# main_chip.net
KiCad netlist of a schematic drawn in Altium Designer
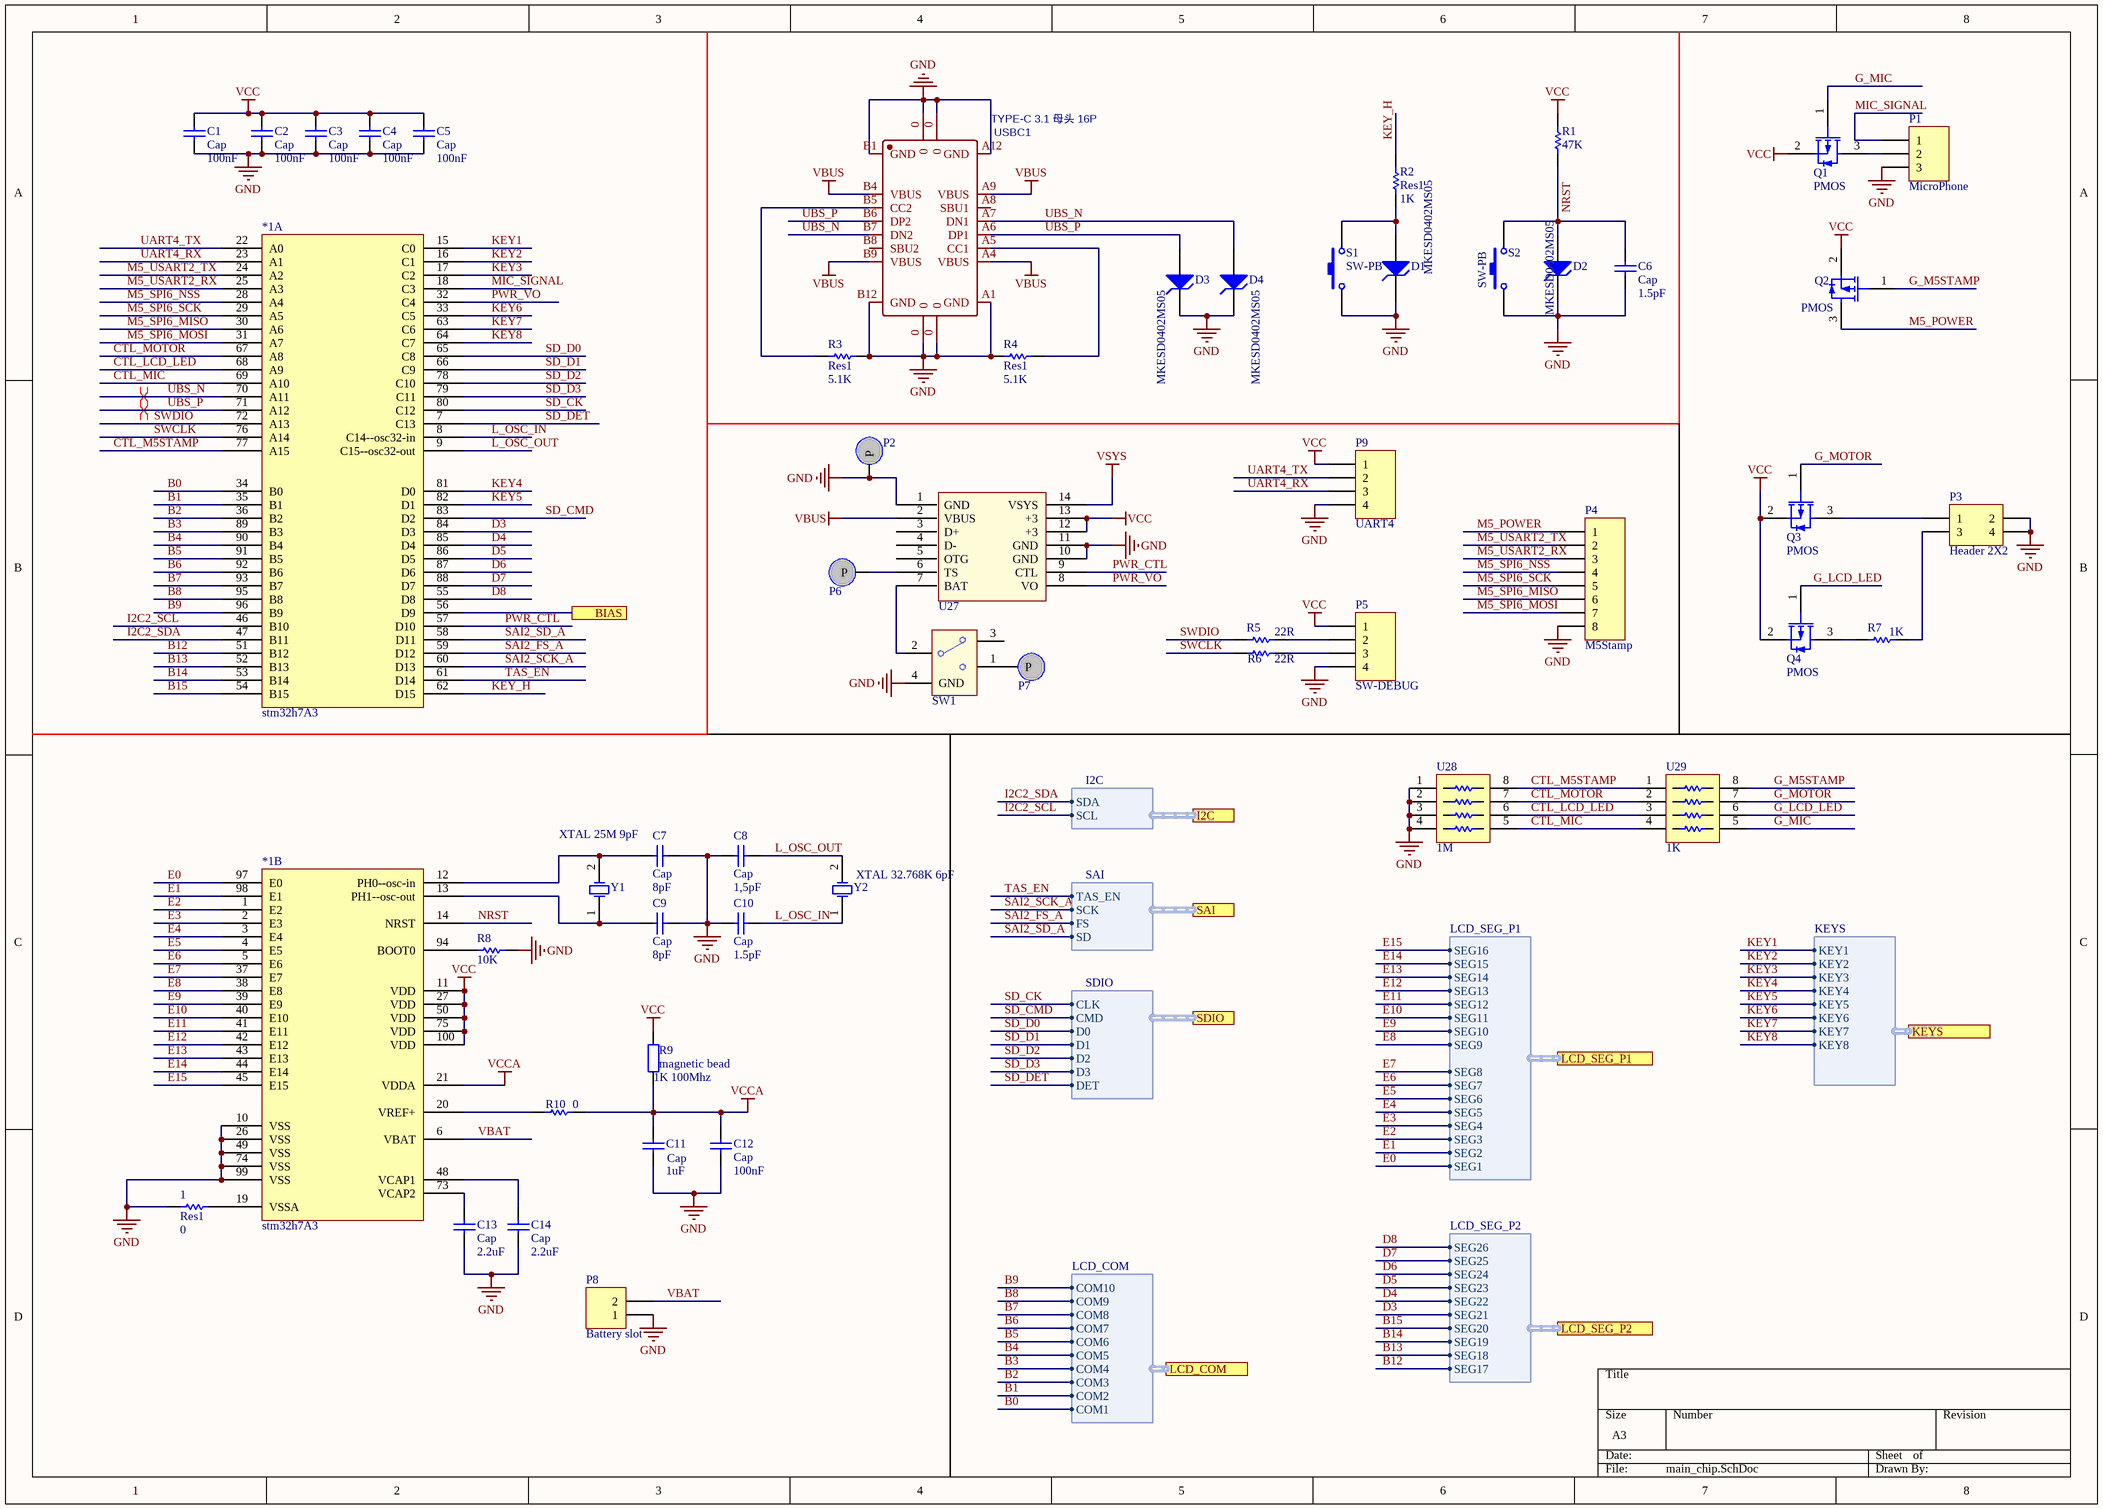
[diagram p0: main_chip.SchDoc]

(export (version "E")
  (design (tool "Eeschema 10.0.6"))
  (components
    (comp (ref "*1")
      (value "stm32h7A3")
      (footprint "CQFP-100")
      (libsource (lib "stm32h743") (part "stm32h743"))
    )
    (comp (ref "1")
      (value "Res1")
      (footprint "0402")
      (description "Resistor")
      (fields (field (name "ALTIUM_VALUE") "0") (field (name "PUBLISHER") "Altium Limited"))
      (libsource (lib "Miscellaneous Devices") (part "Res1"))
    )
    (comp (ref "C1")
      (value "Cap")
      (footprint "0402")
      (description "Capacitor")
      (fields (field (name "ALTIUM_VALUE") "100nF") (field (name "PUBLISHER") "Altium Limited"))
      (libsource (lib "Miscellaneous Devices") (part "Cap"))
    )
    (comp (ref "C2")
      (value "Cap")
      (footprint "0402")
      (description "Capacitor")
      (fields (field (name "ALTIUM_VALUE") "100nF") (field (name "PUBLISHER") "Altium Limited"))
      (libsource (lib "Miscellaneous Devices") (part "Cap"))
    )
    (comp (ref "C3")
      (value "Cap")
      (footprint "0402")
      (description "Capacitor")
      (fields (field (name "ALTIUM_VALUE") "100nF") (field (name "PUBLISHER") "Altium Limited"))
      (libsource (lib "Miscellaneous Devices") (part "Cap"))
    )
    (comp (ref "C4")
      (value "Cap")
      (footprint "0402")
      (description "Capacitor")
      (fields (field (name "ALTIUM_VALUE") "100nF") (field (name "PUBLISHER") "Altium Limited"))
      (libsource (lib "Miscellaneous Devices") (part "Cap"))
    )
    (comp (ref "C5")
      (value "Cap")
      (footprint "0402")
      (description "Capacitor")
      (fields (field (name "ALTIUM_VALUE") "100nF") (field (name "PUBLISHER") "Altium Limited"))
      (libsource (lib "Miscellaneous Devices") (part "Cap"))
    )
    (comp (ref "C6")
      (value "Cap")
      (footprint "0402")
      (description "Capacitor")
      (fields (field (name "ALTIUM_VALUE") "1.5pF") (field (name "PUBLISHER") "Altium Limited"))
      (libsource (lib "Miscellaneous Devices") (part "Cap"))
    )
    (comp (ref "C7")
      (value "Cap")
      (footprint "0402")
      (description "Capacitor")
      (fields (field (name "ALTIUM_VALUE") "8pF") (field (name "PUBLISHER") "Altium Limited"))
      (libsource (lib "Miscellaneous Devices") (part "Cap"))
    )
    (comp (ref "C8")
      (value "Cap")
      (footprint "0402")
      (description "Capacitor")
      (fields (field (name "ALTIUM_VALUE") "1,5pF") (field (name "PUBLISHER") "Altium Limited"))
      (libsource (lib "Miscellaneous Devices") (part "Cap"))
    )
    (comp (ref "C9")
      (value "Cap")
      (footprint "0402")
      (description "Capacitor")
      (fields (field (name "ALTIUM_VALUE") "8pF") (field (name "PUBLISHER") "Altium Limited"))
      (libsource (lib "Miscellaneous Devices") (part "Cap"))
    )
    (comp (ref "C10")
      (value "Cap")
      (footprint "0402")
      (description "Capacitor")
      (fields (field (name "ALTIUM_VALUE") "1.5pF") (field (name "PUBLISHER") "Altium Limited"))
      (libsource (lib "Miscellaneous Devices") (part "Cap"))
    )
    (comp (ref "C11")
      (value "Cap")
      (footprint "6-0805_L")
      (description "Capacitor")
      (fields (field (name "ALTIUM_VALUE") "1uF") (field (name "PUBLISHER") "Altium Limited"))
      (libsource (lib "Miscellaneous Devices") (part "Cap"))
    )
    (comp (ref "C12")
      (value "Cap")
      (footprint "0402")
      (description "Capacitor")
      (fields (field (name "ALTIUM_VALUE") "100nF") (field (name "PUBLISHER") "Altium Limited"))
      (libsource (lib "Miscellaneous Devices") (part "Cap"))
    )
    (comp (ref "C13")
      (value "Cap")
      (footprint "6-0805_L")
      (description "Capacitor")
      (fields (field (name "ALTIUM_VALUE") "2.2uF") (field (name "PUBLISHER") "Altium Limited"))
      (libsource (lib "Miscellaneous Devices") (part "Cap"))
    )
    (comp (ref "C14")
      (value "Cap")
      (footprint "6-0805_L")
      (description "Capacitor")
      (fields (field (name "ALTIUM_VALUE") "2.2uF") (field (name "PUBLISHER") "Altium Limited"))
      (libsource (lib "Miscellaneous Devices") (part "Cap"))
    )
    (comp (ref "D1")
      (value "MKESD0402MS05")
      (footprint "0402")
      (description "Zener Diode")
      (fields (field (name "PUBLISHER") "Altium Limited"))
      (libsource (lib "Miscellaneous Devices") (part "D Zener"))
    )
    (comp (ref "D2")
      (value "MKESD0402MS05")
      (footprint "0402")
      (description "Zener Diode")
      (fields (field (name "PUBLISHER") "Altium Limited"))
      (libsource (lib "Miscellaneous Devices") (part "D Zener"))
    )
    (comp (ref "D3")
      (value "MKESD0402MS05")
      (footprint "0402")
      (description "Zener Diode")
      (fields (field (name "PUBLISHER") "Altium Limited"))
      (libsource (lib "Miscellaneous Devices") (part "D Zener"))
    )
    (comp (ref "D4")
      (value "MKESD0402MS05")
      (footprint "0402")
      (description "Zener Diode")
      (fields (field (name "PUBLISHER") "Altium Limited"))
      (libsource (lib "Miscellaneous Devices") (part "D Zener"))
    )
    (comp (ref "P1")
      (value "MicroPhone")
      (footprint "HDR1X3")
      (description "Header, 3-Pin")
      (fields (field (name "PUBLISHER") "Altium Limited"))
      (libsource (lib "Miscellaneous Connectors") (part "Header 3"))
    )
    (comp (ref "P2") (value "Point") (footprint "Point") (libsource (lib "cl_sch") (part "Point")))
    (comp (ref "P3")
      (value "Header 2X2")
      (footprint "HDR2X2")
      (description "Header, 2-Pin, Dual row")
      (fields (field (name "PUBLISHER") "Altium Limited"))
      (libsource (lib "Miscellaneous Connectors") (part "Header 2X2"))
    )
    (comp (ref "P4")
      (value "M5Stamp")
      (footprint "HDR1X8")
      (description "Header, 8-Pin")
      (fields (field (name "PUBLISHER") "Altium Limited"))
      (libsource (lib "Miscellaneous Connectors") (part "Header 8"))
    )
    (comp (ref "P5")
      (value "SW-DEBUG")
      (footprint "HDR1X4")
      (description "Header, 4-Pin")
      (fields (field (name "PUBLISHER") "Altium Limited"))
      (libsource (lib "Miscellaneous Connectors") (part "Header 4"))
    )
    (comp (ref "P6") (value "Point") (footprint "Point") (libsource (lib "cl_sch") (part "Point")))
    (comp (ref "P7") (value "Point") (footprint "Point") (libsource (lib "cl_sch") (part "Point")))
    (comp (ref "P8")
      (value "Battery slot")
      (footprint "CR1220-SLOT")
      (description "Header, 2-Pin")
      (fields (field (name "PUBLISHER") "Altium Limited"))
      (libsource (lib "Miscellaneous Connectors") (part "Header 2"))
    )
    (comp (ref "P9")
      (value "UART4")
      (footprint "HDR1X4")
      (description "Header, 4-Pin")
      (fields (field (name "PUBLISHER") "Altium Limited"))
      (libsource (lib "Miscellaneous Connectors") (part "Header 4"))
    )
    (comp (ref "Q1") (value "PMOS") (footprint "SOT23-3") (libsource (lib "cl_sch") (part "PMOS")))
    (comp (ref "Q2") (value "PMOS") (footprint "SOT23-3") (libsource (lib "cl_sch") (part "PMOS")))
    (comp (ref "Q3") (value "PMOS") (footprint "SOT23-3") (libsource (lib "cl_sch") (part "PMOS")))
    (comp (ref "Q4") (value "PMOS") (footprint "SOT23-3") (libsource (lib "cl_sch") (part "PMOS")))
    (comp (ref "R1")
      (value "47K")
      (footprint "0402")
      (description "Resistor")
      (fields (field (name "Comment") "Res1") (field (name "PUBLISHER") "Altium Limited"))
      (libsource (lib "Miscellaneous Devices") (part "Res1"))
    )
    (comp (ref "R2")
      (value "Res1")
      (footprint "0402")
      (description "Resistor")
      (fields (field (name "ALTIUM_VALUE") "1K") (field (name "PUBLISHER") "Altium Limited"))
      (libsource (lib "Miscellaneous Devices") (part "Res1"))
    )
    (comp (ref "R3")
      (value "Res1")
      (footprint "0402")
      (description "Resistor")
      (fields (field (name "ALTIUM_VALUE") "5.1K") (field (name "PUBLISHER") "Altium Limited"))
      (libsource (lib "Miscellaneous Devices") (part "Res1"))
    )
    (comp (ref "R4")
      (value "Res1")
      (footprint "0402")
      (description "Resistor")
      (fields (field (name "ALTIUM_VALUE") "5.1K") (field (name "PUBLISHER") "Altium Limited"))
      (libsource (lib "Miscellaneous Devices") (part "Res1"))
    )
    (comp (ref "R5")
      (value "22R")
      (footprint "0402")
      (description "Resistor")
      (fields (field (name "Comment") "Res1") (field (name "PUBLISHER") "Altium Limited"))
      (libsource (lib "Miscellaneous Devices") (part "Res1"))
    )
    (comp (ref "R6")
      (value "22R")
      (footprint "0402")
      (description "Resistor")
      (fields (field (name "Comment") "Res1") (field (name "PUBLISHER") "Altium Limited"))
      (libsource (lib "Miscellaneous Devices") (part "Res1"))
    )
    (comp (ref "R7")
      (value "1K")
      (footprint "0402")
      (description "Resistor")
      (fields (field (name "Comment") "Res1") (field (name "PUBLISHER") "Altium Limited"))
      (libsource (lib "Miscellaneous Devices") (part "Res1"))
    )
    (comp (ref "R8")
      (value "10K")
      (footprint "0402")
      (description "Resistor")
      (fields (field (name "Comment") "Res1") (field (name "PUBLISHER") "Altium Limited"))
      (libsource (lib "Miscellaneous Devices") (part "Res1"))
    )
    (comp (ref "R9")
      (value "magnetic bead")
      (footprint "0402")
      (description "Resistor")
      (fields (field (name "ALTIUM_VALUE") "1K 100Mhz") (field (name "PUBLISHER") "Altium Limited"))
      (libsource (lib "Miscellaneous Devices") (part "Res2"))
    )
    (comp (ref "R10")
      (value "0")
      (footprint "0402")
      (description "Resistor")
      (fields (field (name "Comment") "Res1") (field (name "PUBLISHER") "Altium Limited"))
      (libsource (lib "Miscellaneous Devices") (part "Res1"))
    )
    (comp (ref "S1")
      (value "SW-PB")
      (footprint "BTN_0304")
      (description "Switch")
      (fields (field (name "PUBLISHER") "Altium Limited"))
      (libsource (lib "Miscellaneous Devices") (part "SW-PB"))
    )
    (comp (ref "S2")
      (value "SW-PB")
      (footprint "BTN_0304")
      (description "Switch")
      (fields (field (name "PUBLISHER") "Altium Limited"))
      (libsource (lib "Miscellaneous Devices") (part "SW-PB"))
    )
    (comp (ref "SW1") (value "SK-12D07VG3") (footprint "switch") (libsource (lib "cl_sch") (part "SW-8.6mm")))
    (comp (ref "U27") (value "my_power") (footprint "my_power") (libsource (lib "cl_sch") (part "my_power")))
    (comp (ref "U28") (value "1M") (footprint "0603_RES_BATCH") (libsource (lib "cl_sch") (part "RES_BATCH")))
    (comp (ref "U29") (value "1K") (footprint "0603_RES_BATCH") (libsource (lib "cl_sch") (part "RES_BATCH")))
    (comp (ref "USBC1")
      (value "TYPE-C 3.1 母头 16P")
      (footprint "USB-C-SMD_16P")
      (libsource (lib "type-c-sch") (part "TYPE-C 3.1 母头 16P"))
    )
    (comp (ref "Y1")
      (value "XTAL 25M 9pF")
      (footprint "xtal_5032_25Mhz")
      (description "Crystal Oscillator")
      (fields (field (name "PUBLISHER") "Altium Limited"))
      (libsource (lib "Miscellaneous Devices") (part "XTAL"))
    )
    (comp (ref "Y2")
      (value "XTAL 32.768K 6pF")
      (footprint "xtal_3215_32768")
      (description "Crystal Oscillator")
      (fields (field (name "PUBLISHER") "Altium Limited"))
      (libsource (lib "Miscellaneous Devices") (part "XTAL"))
    )
  )
  (nets
    (net (code "8") (name "/B0") (class "Default")
      (node (ref "*1") (pin "34") (pinfunction "B0_34") (pintype "passive"))
    )
    (net (code "9") (name "/B1") (class "Default")
      (node (ref "*1") (pin "35") (pinfunction "B1_35") (pintype "passive"))
    )
    (net (code "10") (name "/B2") (class "Default")
      (node (ref "*1") (pin "36") (pinfunction "B2_36") (pintype "passive"))
    )
    (net (code "11") (name "/B3") (class "Default")
      (node (ref "*1") (pin "89") (pinfunction "B3_89") (pintype "passive"))
    )
    (net (code "12") (name "/B4") (class "Default")
      (node (ref "*1") (pin "90") (pinfunction "B4_90") (pintype "passive"))
    )
    (net (code "13") (name "/B5") (class "Default")
      (node (ref "*1") (pin "91") (pinfunction "B5_91") (pintype "passive"))
    )
    (net (code "14") (name "/B6") (class "Default")
      (node (ref "*1") (pin "92") (pinfunction "B6_92") (pintype "passive"))
    )
    (net (code "15") (name "/B7") (class "Default")
      (node (ref "*1") (pin "93") (pinfunction "B7_93") (pintype "passive"))
    )
    (net (code "16") (name "/B8") (class "Default")
      (node (ref "*1") (pin "95") (pinfunction "B8_95") (pintype "passive"))
    )
    (net (code "17") (name "/B9") (class "Default")
      (node (ref "*1") (pin "96") (pinfunction "B9_96") (pintype "passive"))
    )
    (net (code "18") (name "/B12") (class "Default")
      (node (ref "*1") (pin "51") (pinfunction "B12_51") (pintype "passive"))
    )
    (net (code "19") (name "/B13") (class "Default")
      (node (ref "*1") (pin "52") (pinfunction "B13_52") (pintype "passive"))
    )
    (net (code "20") (name "/B14") (class "Default")
      (node (ref "*1") (pin "53") (pinfunction "B14_53") (pintype "passive"))
    )
    (net (code "21") (name "/B15") (class "Default")
      (node (ref "*1") (pin "54") (pinfunction "B15_54") (pintype "passive"))
    )
    (net (code "22") (name "/BIAS") (class "Default")
      (node (ref "*1") (pin "56") (pinfunction "D9_56") (pintype "passive"))
    )
    (net (code "23") (name "/CTL_LCD_LED") (class "Default")
      (node (ref "*1") (pin "68") (pinfunction "A9_68") (pintype "passive"))
      (node (ref "U28") (pin "6") (pinfunction "6_6") (pintype "passive"))
      (node (ref "U29") (pin "3") (pinfunction "3_3") (pintype "passive"))
    )
    (net (code "24") (name "/CTL_M5STAMP") (class "Default")
      (node (ref "*1") (pin "77") (pinfunction "A15_77") (pintype "passive"))
      (node (ref "U28") (pin "8") (pinfunction "8_8") (pintype "passive"))
      (node (ref "U29") (pin "1") (pinfunction "1_1") (pintype "passive"))
    )
    (net (code "25") (name "/CTL_MIC") (class "Default")
      (node (ref "*1") (pin "69") (pinfunction "A10_69") (pintype "passive"))
      (node (ref "U28") (pin "5") (pinfunction "5_5") (pintype "passive"))
      (node (ref "U29") (pin "4") (pinfunction "4_4") (pintype "passive"))
    )
    (net (code "26") (name "/CTL_MOTOR") (class "Default")
      (node (ref "*1") (pin "67") (pinfunction "A8_67") (pintype "passive"))
      (node (ref "U28") (pin "7") (pinfunction "7_7") (pintype "passive"))
      (node (ref "U29") (pin "2") (pinfunction "2_2") (pintype "passive"))
    )
    (net (code "27") (name "/D3") (class "Default")
      (node (ref "*1") (pin "84") (pinfunction "D3_84") (pintype "passive"))
    )
    (net (code "28") (name "/D4") (class "Default")
      (node (ref "*1") (pin "85") (pinfunction "D4_85") (pintype "passive"))
    )
    (net (code "29") (name "/D5") (class "Default")
      (node (ref "*1") (pin "86") (pinfunction "D5_86") (pintype "passive"))
    )
    (net (code "30") (name "/D6") (class "Default")
      (node (ref "*1") (pin "87") (pinfunction "D6_87") (pintype "passive"))
    )
    (net (code "31") (name "/D7") (class "Default")
      (node (ref "*1") (pin "88") (pinfunction "D7_88") (pintype "passive"))
    )
    (net (code "32") (name "/D8") (class "Default")
      (node (ref "*1") (pin "55") (pinfunction "D8_55") (pintype "passive"))
    )
    (net (code "33") (name "/E0") (class "Default")
      (node (ref "*1") (pin "97") (pinfunction "E0_97") (pintype "passive"))
    )
    (net (code "34") (name "/E1") (class "Default")
      (node (ref "*1") (pin "98") (pinfunction "E1_98") (pintype "passive"))
    )
    (net (code "35") (name "/E2") (class "Default")
      (node (ref "*1") (pin "1") (pinfunction "E2_1") (pintype "passive"))
    )
    (net (code "36") (name "/E3") (class "Default")
      (node (ref "*1") (pin "2") (pinfunction "E3_2") (pintype "passive"))
    )
    (net (code "37") (name "/E4") (class "Default")
      (node (ref "*1") (pin "3") (pinfunction "E4_3") (pintype "passive"))
    )
    (net (code "38") (name "/E5") (class "Default")
      (node (ref "*1") (pin "4") (pinfunction "E5_4") (pintype "passive"))
    )
    (net (code "39") (name "/E6") (class "Default")
      (node (ref "*1") (pin "5") (pinfunction "E6_5") (pintype "passive"))
    )
    (net (code "40") (name "/E7") (class "Default")
      (node (ref "*1") (pin "37") (pinfunction "E7_37") (pintype "passive"))
    )
    (net (code "41") (name "/E8") (class "Default")
      (node (ref "*1") (pin "38") (pinfunction "E8_38") (pintype "passive"))
    )
    (net (code "42") (name "/E9") (class "Default")
      (node (ref "*1") (pin "39") (pinfunction "E9_39") (pintype "passive"))
    )
    (net (code "43") (name "/E10") (class "Default")
      (node (ref "*1") (pin "40") (pinfunction "E10_40") (pintype "passive"))
    )
    (net (code "44") (name "/E11") (class "Default")
      (node (ref "*1") (pin "41") (pinfunction "E11_41") (pintype "passive"))
    )
    (net (code "45") (name "/E12") (class "Default")
      (node (ref "*1") (pin "42") (pinfunction "E12_42") (pintype "passive"))
    )
    (net (code "46") (name "/E13") (class "Default")
      (node (ref "*1") (pin "43") (pinfunction "E13_43") (pintype "passive"))
    )
    (net (code "47") (name "/E14") (class "Default")
      (node (ref "*1") (pin "44") (pinfunction "E14_44") (pintype "passive"))
    )
    (net (code "48") (name "/E15") (class "Default")
      (node (ref "*1") (pin "45") (pinfunction "E15_45") (pintype "passive"))
    )
    (net (code "49") (name "/G_LCD_LED") (class "Default")
      (node (ref "Q4") (pin "1") (pinfunction "G_1") (pintype "passive"))
      (node (ref "U29") (pin "6") (pinfunction "6_6") (pintype "passive"))
    )
    (net (code "50") (name "/G_M5STAMP") (class "Default")
      (node (ref "Q2") (pin "1") (pinfunction "G_1") (pintype "passive"))
      (node (ref "U29") (pin "8") (pinfunction "8_8") (pintype "passive"))
    )
    (net (code "51") (name "/G_MIC") (class "Default")
      (node (ref "Q1") (pin "1") (pinfunction "G_1") (pintype "passive"))
      (node (ref "U29") (pin "5") (pinfunction "5_5") (pintype "passive"))
    )
    (net (code "52") (name "/G_MOTOR") (class "Default")
      (node (ref "Q3") (pin "1") (pinfunction "G_1") (pintype "passive"))
      (node (ref "U29") (pin "7") (pinfunction "7_7") (pintype "passive"))
    )
    (net (code "53") (name "/I2C2_SCL") (class "Default")
      (node (ref "*1") (pin "46") (pinfunction "B10_46") (pintype "passive"))
    )
    (net (code "54") (name "/I2C2_SDA") (class "Default")
      (node (ref "*1") (pin "47") (pinfunction "B11_47") (pintype "passive"))
    )
    (net (code "55") (name "/KEY1") (class "Default")
      (node (ref "*1") (pin "15") (pinfunction "C0_15") (pintype "passive"))
    )
    (net (code "56") (name "/KEY2") (class "Default")
      (node (ref "*1") (pin "16") (pinfunction "C1_16") (pintype "passive"))
    )
    (net (code "57") (name "/KEY3") (class "Default")
      (node (ref "*1") (pin "17") (pinfunction "C2_17") (pintype "passive"))
    )
    (net (code "58") (name "/KEY4") (class "Default")
      (node (ref "*1") (pin "81") (pinfunction "D0_81") (pintype "passive"))
    )
    (net (code "59") (name "/KEY5") (class "Default")
      (node (ref "*1") (pin "82") (pinfunction "D1_82") (pintype "passive"))
    )
    (net (code "60") (name "/KEY6") (class "Default")
      (node (ref "*1") (pin "33") (pinfunction "C5_33") (pintype "passive"))
    )
    (net (code "61") (name "/KEY7") (class "Default")
      (node (ref "*1") (pin "63") (pinfunction "C6_63") (pintype "passive"))
    )
    (net (code "62") (name "/KEY8") (class "Default")
      (node (ref "*1") (pin "64") (pinfunction "C7_64") (pintype "passive"))
    )
    (net (code "63") (name "/KEY_H") (class "Default")
      (node (ref "*1") (pin "62") (pinfunction "D15_62") (pintype "passive"))
      (node (ref "R2") (pin "1") (pinfunction "1_1") (pintype "passive"))
    )
    (net (code "64") (name "/L_OSC_IN") (class "Default")
      (node (ref "*1") (pin "8") (pinfunction "C14--osc32-in_8") (pintype "passive"))
      (node (ref "C10") (pin "1") (pinfunction "1_1") (pintype "passive"))
      (node (ref "Y2") (pin "1") (pinfunction "OSC1_1") (pintype "passive"))
    )
    (net (code "65") (name "/L_OSC_OUT") (class "Default")
      (node (ref "*1") (pin "9") (pinfunction "C15--osc32-out_9") (pintype "passive"))
      (node (ref "C8") (pin "1") (pinfunction "1_1") (pintype "passive"))
      (node (ref "Y2") (pin "2") (pinfunction "OSC2_2") (pintype "passive"))
    )
    (net (code "66") (name "/M5_POWER") (class "Default")
      (node (ref "P4") (pin "1") (pinfunction "1_1") (pintype "passive"))
      (node (ref "Q2") (pin "3") (pinfunction "D_3") (pintype "passive"))
    )
    (net (code "67") (name "/M5_SPI6_MISO") (class "Default")
      (node (ref "*1") (pin "30") (pinfunction "A6_30") (pintype "passive"))
      (node (ref "P4") (pin "6") (pinfunction "6_6") (pintype "passive"))
    )
    (net (code "68") (name "/M5_SPI6_MOSI") (class "Default")
      (node (ref "*1") (pin "31") (pinfunction "A7_31") (pintype "passive"))
      (node (ref "P4") (pin "7") (pinfunction "7_7") (pintype "passive"))
    )
    (net (code "69") (name "/M5_SPI6_NSS") (class "Default")
      (node (ref "*1") (pin "28") (pinfunction "A4_28") (pintype "passive"))
      (node (ref "P4") (pin "4") (pinfunction "4_4") (pintype "passive"))
    )
    (net (code "70") (name "/M5_SPI6_SCK") (class "Default")
      (node (ref "*1") (pin "29") (pinfunction "A5_29") (pintype "passive"))
      (node (ref "P4") (pin "5") (pinfunction "5_5") (pintype "passive"))
    )
    (net (code "71") (name "/M5_USART2_RX") (class "Default")
      (node (ref "*1") (pin "25") (pinfunction "A3_25") (pintype "passive"))
      (node (ref "P4") (pin "3") (pinfunction "3_3") (pintype "passive"))
    )
    (net (code "72") (name "/M5_USART2_TX") (class "Default")
      (node (ref "*1") (pin "24") (pinfunction "A2_24") (pintype "passive"))
      (node (ref "P4") (pin "2") (pinfunction "2_2") (pintype "passive"))
    )
    (net (code "73") (name "/MIC_SIGNAL") (class "Default")
      (node (ref "*1") (pin "18") (pinfunction "C3_18") (pintype "passive"))
      (node (ref "P1") (pin "1") (pinfunction "1_1") (pintype "passive"))
    )
    (net (code "74") (name "/NRST") (class "Default")
      (node (ref "*1") (pin "14") (pinfunction "NRST_14") (pintype "passive"))
      (node (ref "C6") (pin "1") (pinfunction "1_1") (pintype "passive"))
      (node (ref "D2") (pin "1") (pinfunction "A_1") (pintype "passive"))
      (node (ref "R1") (pin "2") (pinfunction "2_2") (pintype "passive"))
      (node (ref "S2") (pin "2") (pinfunction "2_2") (pintype "passive"))
    )
    (net (code "75") (name "/PWR_CTL") (class "Default")
      (node (ref "*1") (pin "57") (pinfunction "D10_57") (pintype "passive"))
      (node (ref "U27") (pin "9") (pinfunction "CTL_9") (pintype "passive"))
    )
    (net (code "76") (name "/PWR_VO") (class "Default")
      (node (ref "*1") (pin "32") (pinfunction "C4_32") (pintype "passive"))
      (node (ref "U27") (pin "8") (pinfunction "VO_8") (pintype "passive"))
    )
    (net (code "77") (name "/SAI2_FS_A") (class "Default")
      (node (ref "*1") (pin "59") (pinfunction "D12_59") (pintype "passive"))
    )
    (net (code "78") (name "/SAI2_SCK_A") (class "Default")
      (node (ref "*1") (pin "60") (pinfunction "D13_60") (pintype "passive"))
    )
    (net (code "79") (name "/SAI2_SD_A") (class "Default")
      (node (ref "*1") (pin "58") (pinfunction "D11_58") (pintype "passive"))
    )
    (net (code "80") (name "/SD_CK") (class "Default")
      (node (ref "*1") (pin "80") (pinfunction "C12_80") (pintype "passive"))
    )
    (net (code "81") (name "/SD_CMD") (class "Default")
      (node (ref "*1") (pin "83") (pinfunction "D2_83") (pintype "passive"))
    )
    (net (code "82") (name "/SD_D0") (class "Default")
      (node (ref "*1") (pin "65") (pinfunction "C8_65") (pintype "passive"))
    )
    (net (code "83") (name "/SD_D1") (class "Default")
      (node (ref "*1") (pin "66") (pinfunction "C9_66") (pintype "passive"))
    )
    (net (code "84") (name "/SD_D2") (class "Default")
      (node (ref "*1") (pin "78") (pinfunction "C10_78") (pintype "passive"))
    )
    (net (code "85") (name "/SD_D3") (class "Default")
      (node (ref "*1") (pin "79") (pinfunction "C11_79") (pintype "passive"))
    )
    (net (code "86") (name "/SD_DET") (class "Default")
      (node (ref "*1") (pin "7") (pinfunction "C13_7") (pintype "passive"))
    )
    (net (code "87") (name "/SWCLK") (class "Default")
      (node (ref "*1") (pin "76") (pinfunction "A14_76") (pintype "passive"))
      (node (ref "R6") (pin "1") (pinfunction "1_1") (pintype "passive"))
    )
    (net (code "88") (name "/SWDIO") (class "Default")
      (node (ref "*1") (pin "72") (pinfunction "A13_72") (pintype "passive"))
      (node (ref "R5") (pin "1") (pinfunction "1_1") (pintype "passive"))
    )
    (net (code "89") (name "/TAS_EN") (class "Default")
      (node (ref "*1") (pin "61") (pinfunction "D14_61") (pintype "passive"))
    )
    (net (code "90") (name "/UART4_RX") (class "Default")
      (node (ref "*1") (pin "23") (pinfunction "A1_23") (pintype "passive"))
      (node (ref "P9") (pin "3") (pinfunction "3_3") (pintype "passive"))
    )
    (net (code "91") (name "/UART4_TX") (class "Default")
      (node (ref "*1") (pin "22") (pinfunction "A0_22") (pintype "passive"))
      (node (ref "P9") (pin "2") (pinfunction "2_2") (pintype "passive"))
    )
    (net (code "92") (name "/UBS_N") (class "Default")
      (node (ref "*1") (pin "70") (pinfunction "A11_70") (pintype "passive"))
      (node (ref "D4") (pin "1") (pinfunction "A_1") (pintype "passive"))
      (node (ref "USBC1") (pin "A7") (pinfunction "DN1_A7") (pintype "passive"))
      (node (ref "USBC1") (pin "B7") (pinfunction "DN2_B7") (pintype "passive"))
    )
    (net (code "93") (name "/UBS_P") (class "Default")
      (node (ref "*1") (pin "71") (pinfunction "A12_71") (pintype "passive"))
      (node (ref "D3") (pin "1") (pinfunction "A_1") (pintype "passive"))
      (node (ref "USBC1") (pin "A6") (pinfunction "DP1_A6") (pintype "passive"))
      (node (ref "USBC1") (pin "B6") (pinfunction "DP2_B6") (pintype "passive"))
    )
    (net (code "94") (name "/VBAT") (class "Default")
      (node (ref "*1") (pin "6") (pinfunction "VBAT_6") (pintype "passive"))
      (node (ref "P8") (pin "2") (pinfunction "2_2") (pintype "passive"))
    )
    (net (code "102") (name "GND") (class "Default")
      (node (ref "*1") (pin "10") (pinfunction "VSS_10") (pintype "passive"))
      (node (ref "*1") (pin "26") (pinfunction "VSS_26") (pintype "passive"))
      (node (ref "*1") (pin "49") (pinfunction "VSS_49") (pintype "passive"))
      (node (ref "*1") (pin "74") (pinfunction "VSS_74") (pintype "passive"))
      (node (ref "*1") (pin "99") (pinfunction "VSS_99") (pintype "passive"))
      (node (ref "1") (pin "1") (pinfunction "1_1") (pintype "passive"))
      (node (ref "C1") (pin "2") (pinfunction "2_2") (pintype "passive"))
      (node (ref "C10") (pin "2") (pinfunction "2_2") (pintype "passive"))
      (node (ref "C11") (pin "1") (pinfunction "1_1") (pintype "passive"))
      (node (ref "C12") (pin "1") (pinfunction "1_1") (pintype "passive"))
      (node (ref "C13") (pin "1") (pinfunction "1_1") (pintype "passive"))
      (node (ref "C14") (pin "2") (pinfunction "2_2") (pintype "passive"))
      (node (ref "C2") (pin "2") (pinfunction "2_2") (pintype "passive"))
      (node (ref "C3") (pin "2") (pinfunction "2_2") (pintype "passive"))
      (node (ref "C4") (pin "2") (pinfunction "2_2") (pintype "passive"))
      (node (ref "C5") (pin "2") (pinfunction "2_2") (pintype "passive"))
      (node (ref "C6") (pin "2") (pinfunction "2_2") (pintype "passive"))
      (node (ref "C7") (pin "1") (pinfunction "1_1") (pintype "passive"))
      (node (ref "C8") (pin "2") (pinfunction "2_2") (pintype "passive"))
      (node (ref "C9") (pin "1") (pinfunction "1_1") (pintype "passive"))
      (node (ref "D1") (pin "2") (pinfunction "K_2") (pintype "passive"))
      (node (ref "D2") (pin "2") (pinfunction "K_2") (pintype "passive"))
      (node (ref "D3") (pin "2") (pinfunction "K_2") (pintype "passive"))
      (node (ref "D4") (pin "2") (pinfunction "K_2") (pintype "passive"))
      (node (ref "P1") (pin "3") (pinfunction "3_3") (pintype "passive"))
      (node (ref "P2") (pin "1") (pinfunction "P_1") (pintype "passive"))
      (node (ref "P3") (pin "2") (pinfunction "2_2") (pintype "passive"))
      (node (ref "P3") (pin "4") (pinfunction "4_4") (pintype "passive"))
      (node (ref "P4") (pin "8") (pinfunction "8_8") (pintype "passive"))
      (node (ref "P5") (pin "4") (pinfunction "4_4") (pintype "passive"))
      (node (ref "P8") (pin "1") (pinfunction "1_1") (pintype "passive"))
      (node (ref "P9") (pin "4") (pinfunction "4_4") (pintype "passive"))
      (node (ref "R3") (pin "1") (pinfunction "1_1") (pintype "passive"))
      (node (ref "R4") (pin "2") (pinfunction "2_2") (pintype "passive"))
      (node (ref "R8") (pin "1") (pinfunction "1_1") (pintype "passive"))
      (node (ref "S1") (pin "1") (pinfunction "1_1") (pintype "passive"))
      (node (ref "S2") (pin "1") (pinfunction "1_1") (pintype "passive"))
      (node (ref "SW1") (pin "4") (pinfunction "GND_4") (pintype "passive"))
      (node (ref "U27") (pin "1") (pinfunction "GND_1") (pintype "passive"))
      (node (ref "U27") (pin "10") (pinfunction "GND_10") (pintype "passive"))
      (node (ref "U27") (pin "11") (pinfunction "GND_11") (pintype "passive"))
      (node (ref "U28") (pin "1") (pinfunction "1_1") (pintype "passive"))
      (node (ref "U28") (pin "2") (pinfunction "2_2") (pintype "passive"))
      (node (ref "U28") (pin "3") (pinfunction "3_3") (pintype "passive"))
      (node (ref "U28") (pin "4") (pinfunction "4_4") (pintype "passive"))
      (node (ref "USBC1") (pin "0") (pinfunction "0_0") (pintype "passive"))
      (node (ref "USBC1") (pin "A1") (pinfunction "GND_A1") (pintype "passive"))
      (node (ref "USBC1") (pin "A12") (pinfunction "GND_A12") (pintype "passive"))
      (node (ref "USBC1") (pin "B1") (pinfunction "GND_B1") (pintype "passive"))
      (node (ref "USBC1") (pin "B12") (pinfunction "GND_B12") (pintype "passive"))
    )
    (net (code "103") (name "Net-(*1B-BOOT0)") (class "Default")
      (node (ref "*1") (pin "94") (pinfunction "BOOT0_94") (pintype "passive"))
      (node (ref "R8") (pin "2") (pinfunction "2_2") (pintype "passive"))
    )
    (net (code "104") (name "Net-(*1B-PH0--osc-out)") (class "Default")
      (node (ref "*1") (pin "12") (pinfunction "PH0--osc-out_12") (pintype "passive"))
      (node (ref "C7") (pin "2") (pinfunction "2_2") (pintype "passive"))
      (node (ref "Y1") (pin "2") (pinfunction "OSC2_2") (pintype "passive"))
    )
    (net (code "105") (name "Net-(*1B-PH1--osc-out)") (class "Default")
      (node (ref "*1") (pin "13") (pinfunction "PH1--osc-out_13") (pintype "passive"))
      (node (ref "C9") (pin "2") (pinfunction "2_2") (pintype "passive"))
      (node (ref "Y1") (pin "1") (pinfunction "OSC1_1") (pintype "passive"))
    )
    (net (code "106") (name "Net-(*1B-VCAP1)") (class "Default")
      (node (ref "*1") (pin "48") (pinfunction "VCAP1_48") (pintype "passive"))
      (node (ref "C14") (pin "1") (pinfunction "1_1") (pintype "passive"))
    )
    (net (code "107") (name "Net-(*1B-VCAP2)") (class "Default")
      (node (ref "*1") (pin "73") (pinfunction "VCAP2_73") (pintype "passive"))
      (node (ref "C13") (pin "2") (pinfunction "2_2") (pintype "passive"))
    )
    (net (code "108") (name "Net-(*1B-VREF+)") (class "Default")
      (node (ref "*1") (pin "20") (pinfunction "VREF+_20") (pintype "passive"))
      (node (ref "R10") (pin "2") (pinfunction "2_2") (pintype "passive"))
    )
    (net (code "109") (name "Net-(*1B-VSSA)") (class "Default")
      (node (ref "*1") (pin "19") (pinfunction "VSSA_19") (pintype "passive"))
      (node (ref "1") (pin "2") (pinfunction "2_2") (pintype "passive"))
    )
    (net (code "110") (name "Net-(D1-A)") (class "Default")
      (node (ref "D1") (pin "1") (pinfunction "A_1") (pintype "passive"))
      (node (ref "R2") (pin "2") (pinfunction "2_2") (pintype "passive"))
      (node (ref "S1") (pin "2") (pinfunction "2_2") (pintype "passive"))
    )
    (net (code "111") (name "Net-(P3-Pad3)") (class "Default")
      (node (ref "P3") (pin "3") (pinfunction "3_3") (pintype "passive"))
      (node (ref "R7") (pin "1") (pinfunction "1_1") (pintype "passive"))
    )
    (net (code "112") (name "Net-(P5-Pad2)") (class "Default")
      (node (ref "P5") (pin "2") (pinfunction "2_2") (pintype "passive"))
      (node (ref "R5") (pin "2") (pinfunction "2_2") (pintype "passive"))
    )
    (net (code "113") (name "Net-(P5-Pad3)") (class "Default")
      (node (ref "P5") (pin "3") (pinfunction "3_3") (pintype "passive"))
      (node (ref "R6") (pin "2") (pinfunction "2_2") (pintype "passive"))
    )
    (net (code "114") (name "Net-(P6-P)") (class "Default")
      (node (ref "P6") (pin "1") (pinfunction "P_1") (pintype "passive"))
      (node (ref "U27") (pin "6") (pinfunction "TS_6") (pintype "passive"))
    )
    (net (code "115") (name "Net-(P7-P)") (class "Default")
      (node (ref "P7") (pin "1") (pinfunction "P_1") (pintype "passive"))
      (node (ref "SW1") (pin "1") (pinfunction "1_1") (pintype "passive"))
    )
    (net (code "116") (name "Net-(Q1-D)") (class "Default")
      (node (ref "P1") (pin "2") (pinfunction "2_2") (pintype "passive"))
      (node (ref "Q1") (pin "3") (pinfunction "D_3") (pintype "passive"))
    )
    (net (code "117") (name "Net-(Q3-D)") (class "Default")
      (node (ref "P3") (pin "1") (pinfunction "1_1") (pintype "passive"))
      (node (ref "Q3") (pin "3") (pinfunction "D_3") (pintype "passive"))
    )
    (net (code "118") (name "Net-(Q4-D)") (class "Default")
      (node (ref "Q4") (pin "3") (pinfunction "D_3") (pintype "passive"))
      (node (ref "R7") (pin "2") (pinfunction "2_2") (pintype "passive"))
    )
    (net (code "119") (name "Net-(U27-BAT)") (class "Default")
      (node (ref "SW1") (pin "2") (pinfunction "2_2") (pintype "passive"))
      (node (ref "U27") (pin "7") (pinfunction "BAT_7") (pintype "passive"))
    )
    (net (code "120") (name "Net-(USBC1-CC1)") (class "Default")
      (node (ref "R4") (pin "1") (pinfunction "1_1") (pintype "passive"))
      (node (ref "USBC1") (pin "A5") (pinfunction "CC1_A5") (pintype "passive"))
    )
    (net (code "121") (name "Net-(USBC1-CC2)") (class "Default")
      (node (ref "R3") (pin "2") (pinfunction "2_2") (pintype "passive"))
      (node (ref "USBC1") (pin "B5") (pinfunction "CC2_B5") (pintype "passive"))
    )
    (net (code "122") (name "VBUS") (class "Default")
      (node (ref "U27") (pin "2") (pinfunction "VBUS_2") (pintype "passive"))
      (node (ref "USBC1") (pin "A4") (pinfunction "VBUS_A4") (pintype "passive"))
      (node (ref "USBC1") (pin "A9") (pinfunction "VBUS_A9") (pintype "passive"))
      (node (ref "USBC1") (pin "B4") (pinfunction "VBUS_B4") (pintype "passive"))
      (node (ref "USBC1") (pin "B9") (pinfunction "VBUS_B9") (pintype "passive"))
    )
    (net (code "123") (name "VCC") (class "Default")
      (node (ref "*1") (pin "100") (pinfunction "VDD_100") (pintype "passive"))
      (node (ref "*1") (pin "11") (pinfunction "VDD_11") (pintype "passive"))
      (node (ref "*1") (pin "27") (pinfunction "VDD_27") (pintype "passive"))
      (node (ref "*1") (pin "50") (pinfunction "VDD_50") (pintype "passive"))
      (node (ref "*1") (pin "75") (pinfunction "VDD_75") (pintype "passive"))
      (node (ref "C1") (pin "1") (pinfunction "1_1") (pintype "passive"))
      (node (ref "C2") (pin "1") (pinfunction "1_1") (pintype "passive"))
      (node (ref "C3") (pin "1") (pinfunction "1_1") (pintype "passive"))
      (node (ref "C4") (pin "1") (pinfunction "1_1") (pintype "passive"))
      (node (ref "C5") (pin "1") (pinfunction "1_1") (pintype "passive"))
      (node (ref "P5") (pin "1") (pinfunction "1_1") (pintype "passive"))
      (node (ref "P9") (pin "1") (pinfunction "1_1") (pintype "passive"))
      (node (ref "Q1") (pin "2") (pinfunction "S_2") (pintype "passive"))
      (node (ref "Q2") (pin "2") (pinfunction "S_2") (pintype "passive"))
      (node (ref "Q3") (pin "2") (pinfunction "S_2") (pintype "passive"))
      (node (ref "Q4") (pin "2") (pinfunction "S_2") (pintype "passive"))
      (node (ref "R1") (pin "1") (pinfunction "1_1") (pintype "passive"))
      (node (ref "R9") (pin "2") (pinfunction "2_2") (pintype "passive"))
      (node (ref "U27") (pin "12") (pinfunction "+3_12") (pintype "passive"))
      (node (ref "U27") (pin "13") (pinfunction "+3_13") (pintype "passive"))
    )
    (net (code "124") (name "VCCA") (class "Default")
      (node (ref "*1") (pin "21") (pinfunction "VDDA_21") (pintype "passive"))
      (node (ref "C11") (pin "2") (pinfunction "2_2") (pintype "passive"))
      (node (ref "C12") (pin "2") (pinfunction "2_2") (pintype "passive"))
      (node (ref "R10") (pin "1") (pinfunction "1_1") (pintype "passive"))
      (node (ref "R9") (pin "1") (pinfunction "1_1") (pintype "passive"))
    )
    (net (code "125") (name "VSYS") (class "Default")
      (node (ref "U27") (pin "14") (pinfunction "VSYS_14") (pintype "passive"))
    )
    (net (code "126") (name "unconnected-(SW1-Pad3)") (class "Default")
      (node (ref "SW1") (pin "3") (pinfunction "3_3") (pintype "passive"))
    )
    (net (code "127") (name "unconnected-(U27-D+-Pad3)") (class "Default")
      (node (ref "U27") (pin "3") (pinfunction "D+_3") (pintype "passive"))
    )
    (net (code "128") (name "unconnected-(U27-D--Pad4)") (class "Default")
      (node (ref "U27") (pin "4") (pinfunction "D-_4") (pintype "passive"))
    )
    (net (code "129") (name "unconnected-(U27-OTG-Pad5)") (class "Default")
      (node (ref "U27") (pin "5") (pinfunction "OTG_5") (pintype "passive"))
    )
    (net (code "130") (name "unconnected-(USBC1-SBU1-PadA8)") (class "Default")
      (node (ref "USBC1") (pin "A8") (pinfunction "SBU1_A8") (pintype "passive"))
    )
    (net (code "131") (name "unconnected-(USBC1-SBU2-PadB8)") (class "Default")
      (node (ref "USBC1") (pin "B8") (pinfunction "SBU2_B8") (pintype "passive"))
    )
  )
)
